# Sheet1.net
KiCad netlist of a schematic drawn in Altium Designer
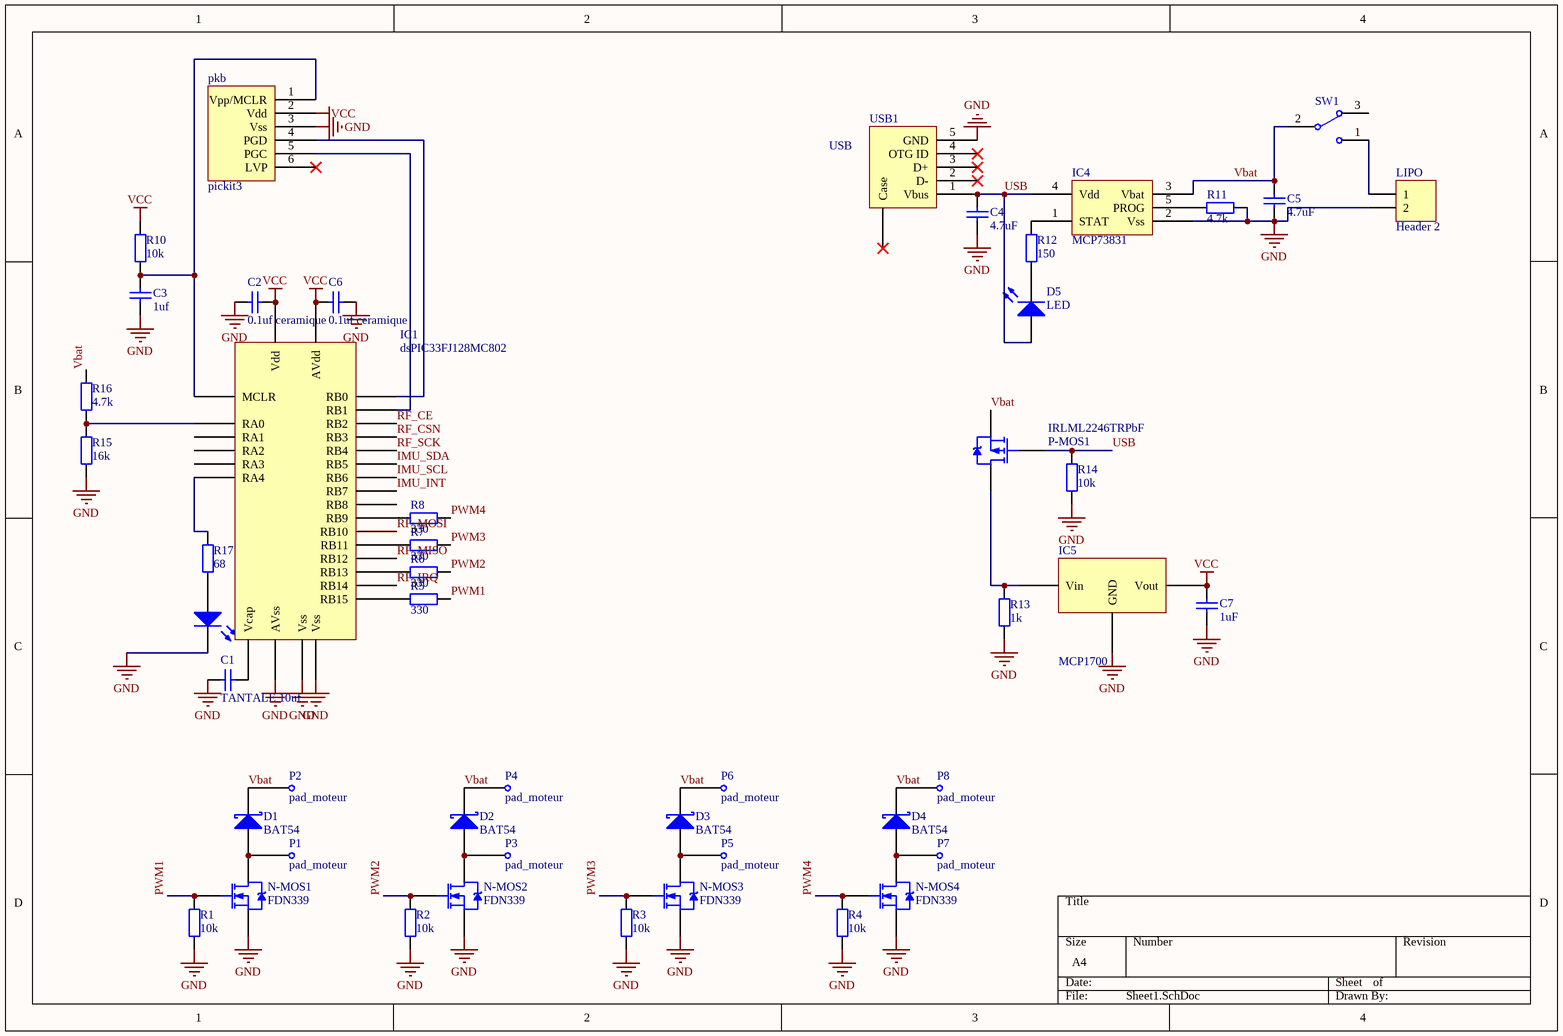
[diagram p0: Sheet1.SchDoc]

(export (version "E")
  (design (tool "Eeschema 10.0.6"))
  (components
    (comp (ref "C1")
      (value "TANTALE 10uf")
      (footprint "cms805")
      (libsource (lib "Integrated_Library1") (part "Capa"))
    )
    (comp (ref "C2")
      (value "0.1uf ceramique")
      (footprint "cms805")
      (libsource (lib "Integrated_Library1") (part "Capa"))
    )
    (comp (ref "C3") (value "1uf") (footprint "cms805") (libsource (lib "Integrated_Library1") (part "Capa")))
    (comp (ref "C4")
      (value "4.7uF")
      (footprint "cms805")
      (libsource (lib "Integrated_Library1") (part "Capa"))
    )
    (comp (ref "C5")
      (value "4.7uF")
      (footprint "cms805")
      (libsource (lib "Integrated_Library1") (part "Capa"))
    )
    (comp (ref "C6")
      (value "0.1uf ceramique")
      (footprint "cms805")
      (libsource (lib "Integrated_Library1") (part "Capa"))
    )
    (comp (ref "C7") (value "1uF") (footprint "cms805") (libsource (lib "Integrated_Library1") (part "Capa")))
    (comp (ref "D1")
      (value "BAT54")
      (footprint "SOT23")
      (libsource (lib "Integrated_Library1") (part "Schottky BAT54"))
    )
    (comp (ref "D2")
      (value "BAT54")
      (footprint "SOT23")
      (libsource (lib "Integrated_Library1") (part "Schottky BAT54"))
    )
    (comp (ref "D3")
      (value "BAT54")
      (footprint "SOT23")
      (libsource (lib "Integrated_Library1") (part "Schottky BAT54"))
    )
    (comp (ref "D4")
      (value "BAT54")
      (footprint "SOT23")
      (libsource (lib "Integrated_Library1") (part "Schottky BAT54"))
    )
    (comp (ref "D5") (value "LED") (footprint "cms1206") (libsource (lib "Integrated_Library1") (part "LED")))
    (comp (ref "D6") (value "LED") (footprint "cms1206") (libsource (lib "Integrated_Library1") (part "LED")))
    (comp (ref "IC1")
      (value "dsPIC33FJ128MC802")
      (footprint "28QFN-S")
      (libsource (lib "Integrated_Library1") (part "dsPIC33FJ128MC802"))
    )
    (comp (ref "IC4")
      (value "MCP73831")
      (footprint "SOT23-5")
      (libsource (lib "Integrated_Library1") (part "MCP73831 Li-Po"))
    )
    (comp (ref "IC5")
      (value "MCP1700")
      (footprint "SOT89")
      (libsource (lib "Integrated_Library1") (part "MCP1700"))
    )
    (comp (ref "IRLML2246TRPbF")
      (value "P-MOS1")
      (footprint "SOT23")
      (libsource (lib "Integrated_Library1") (part "P-MOS"))
    )
    (comp (ref "LIPO")
      (value "Header 2")
      (footprint "HDR1X2")
      (description "Header, 2-Pin")
      (fields (field (name "PUBLISHER") "Altium Limited"))
      (libsource (lib "Miscellaneous Connectors") (part "Header 2"))
    )
    (comp (ref "N-MOS1")
      (value "FDN339")
      (footprint "SuperSOT")
      (libsource (lib "Integrated_Library1") (part "N-MOS FDN339"))
    )
    (comp (ref "N-MOS2")
      (value "FDN339")
      (footprint "SuperSOT")
      (libsource (lib "Integrated_Library1") (part "N-MOS FDN339"))
    )
    (comp (ref "N-MOS3")
      (value "FDN339")
      (footprint "SuperSOT")
      (libsource (lib "Integrated_Library1") (part "N-MOS FDN339"))
    )
    (comp (ref "N-MOS4")
      (value "FDN339")
      (footprint "SuperSOT")
      (libsource (lib "Integrated_Library1") (part "N-MOS FDN339"))
    )
    (comp (ref "P1")
      (value "pad_moteur")
      (footprint "PAD")
      (libsource (lib "Integrated_Library1") (part "pad_moteur"))
    )
    (comp (ref "P2")
      (value "pad_moteur")
      (footprint "PAD")
      (libsource (lib "Integrated_Library1") (part "pad_moteur"))
    )
    (comp (ref "P3")
      (value "pad_moteur")
      (footprint "PAD")
      (libsource (lib "Integrated_Library1") (part "pad_moteur"))
    )
    (comp (ref "P4")
      (value "pad_moteur")
      (footprint "PAD")
      (libsource (lib "Integrated_Library1") (part "pad_moteur"))
    )
    (comp (ref "P5")
      (value "pad_moteur")
      (footprint "PAD")
      (libsource (lib "Integrated_Library1") (part "pad_moteur"))
    )
    (comp (ref "P6")
      (value "pad_moteur")
      (footprint "PAD")
      (libsource (lib "Integrated_Library1") (part "pad_moteur"))
    )
    (comp (ref "P7")
      (value "pad_moteur")
      (footprint "PAD")
      (libsource (lib "Integrated_Library1") (part "pad_moteur"))
    )
    (comp (ref "P8")
      (value "pad_moteur")
      (footprint "PAD")
      (libsource (lib "Integrated_Library1") (part "pad_moteur"))
    )
    (comp (ref "pkb")
      (value "pickit3")
      (footprint "pickit3")
      (libsource (lib "Integrated_Library1") (part "pickit3"))
    )
    (comp (ref "R1")
      (value "10k")
      (footprint "cms805")
      (libsource (lib "Integrated_Library1") (part "Resistance"))
    )
    (comp (ref "R2")
      (value "10k")
      (footprint "cms805")
      (libsource (lib "Integrated_Library1") (part "Resistance"))
    )
    (comp (ref "R3")
      (value "10k")
      (footprint "cms805")
      (libsource (lib "Integrated_Library1") (part "Resistance"))
    )
    (comp (ref "R4")
      (value "10k")
      (footprint "cms805")
      (libsource (lib "Integrated_Library1") (part "Resistance"))
    )
    (comp (ref "R5") (value "330") (footprint "cms805") (libsource (lib "") (part "Resistance_1")))
    (comp (ref "R6") (value "330") (footprint "cms805") (libsource (lib "") (part "Resistance_1")))
    (comp (ref "R7") (value "330") (footprint "cms805") (libsource (lib "") (part "Resistance_1")))
    (comp (ref "R8") (value "330") (footprint "cms805") (libsource (lib "") (part "Resistance_1")))
    (comp (ref "R10")
      (value "10k")
      (footprint "cms805")
      (libsource (lib "Integrated_Library1") (part "Resistance"))
    )
    (comp (ref "R11") (value "4.7k") (footprint "cms805") (libsource (lib "") (part "Resistance_2")))
    (comp (ref "R12") (value "150") (footprint "cms805") (libsource (lib "") (part "Resistance_3")))
    (comp (ref "R13")
      (value "1k")
      (footprint "cms805")
      (libsource (lib "Integrated_Library1") (part "Resistance"))
    )
    (comp (ref "R14")
      (value "10k")
      (footprint "cms805")
      (libsource (lib "Integrated_Library1") (part "Resistance"))
    )
    (comp (ref "R15")
      (value "16k")
      (footprint "cms805")
      (libsource (lib "Integrated_Library1") (part "Resistance"))
    )
    (comp (ref "R16")
      (value "4.7k")
      (footprint "cms805")
      (libsource (lib "Integrated_Library1") (part "Resistance"))
    )
    (comp (ref "R17")
      (value "68")
      (footprint "cms805")
      (libsource (lib "Integrated_Library1") (part "Resistance"))
    )
    (comp (ref "SW1")
      (value "~")
      (footprint "inverseur")
      (libsource (lib "Integrated_Library1") (part "switch"))
    )
    (comp (ref "USB1")
      (value "USB")
      (footprint "USB_con")
      (libsource (lib "Integrated_Library1") (part "USB"))
    )
  )
  (nets
    (net (code "1") (name "/IMU_INT") (class "Default")
      (node (ref "IC1") (pin "16") (pinfunction "RB7_16") (pintype "passive"))
    )
    (net (code "2") (name "/IMU_SCL") (class "Default")
      (node (ref "IC1") (pin "15") (pinfunction "RB6_15") (pintype "passive"))
    )
    (net (code "3") (name "/IMU_SDA") (class "Default")
      (node (ref "IC1") (pin "14") (pinfunction "RB5_14") (pintype "passive"))
    )
    (net (code "4") (name "/PWM1") (class "Default")
      (node (ref "N-MOS1") (pin "1") (pinfunction "G_1") (pintype "passive"))
      (node (ref "R1") (pin "2") (pinfunction "2_2") (pintype "passive"))
      (node (ref "R5") (pin "2") (pinfunction "2_2") (pintype "passive"))
    )
    (net (code "5") (name "/PWM2") (class "Default")
      (node (ref "N-MOS2") (pin "1") (pinfunction "G_1") (pintype "passive"))
      (node (ref "R2") (pin "2") (pinfunction "2_2") (pintype "passive"))
      (node (ref "R6") (pin "2") (pinfunction "2_2") (pintype "passive"))
    )
    (net (code "6") (name "/PWM3") (class "Default")
      (node (ref "N-MOS3") (pin "1") (pinfunction "G_1") (pintype "passive"))
      (node (ref "R3") (pin "2") (pinfunction "2_2") (pintype "passive"))
      (node (ref "R7") (pin "2") (pinfunction "2_2") (pintype "passive"))
    )
    (net (code "7") (name "/PWM4") (class "Default")
      (node (ref "N-MOS4") (pin "1") (pinfunction "G_1") (pintype "passive"))
      (node (ref "R4") (pin "2") (pinfunction "2_2") (pintype "passive"))
      (node (ref "R8") (pin "2") (pinfunction "2_2") (pintype "passive"))
    )
    (net (code "8") (name "/RF_CE") (class "Default")
      (node (ref "IC1") (pin "6") (pinfunction "RB2_6") (pintype "passive"))
    )
    (net (code "9") (name "/RF_CSN") (class "Default")
      (node (ref "IC1") (pin "7") (pinfunction "RB3_7") (pintype "passive"))
    )
    (net (code "10") (name "/RF_IRQ") (class "Default")
      (node (ref "IC1") (pin "25") (pinfunction "RB14_25") (pintype "passive"))
    )
    (net (code "11") (name "/RF_MISO") (class "Default")
      (node (ref "IC1") (pin "23") (pinfunction "RB12_23") (pintype "passive"))
    )
    (net (code "12") (name "/RF_MOSI") (class "Default")
      (node (ref "IC1") (pin "21") (pinfunction "RB10_21") (pintype "passive"))
    )
    (net (code "13") (name "/RF_SCK") (class "Default")
      (node (ref "IC1") (pin "11") (pinfunction "RB4_11") (pintype "passive"))
    )
    (net (code "14") (name "/USB") (class "Default")
      (node (ref "C4") (pin "2") (pinfunction "2_2") (pintype "passive"))
      (node (ref "D5") (pin "1") (pinfunction "A_1") (pintype "passive"))
      (node (ref "IC4") (pin "4") (pinfunction "Vdd_4") (pintype "passive"))
      (node (ref "IRLML2246TRPbF") (pin "1") (pinfunction "G_1") (pintype "passive"))
      (node (ref "R14") (pin "2") (pinfunction "2_2") (pintype "passive"))
      (node (ref "USB1") (pin "1") (pinfunction "Vbus_1") (pintype "passive"))
    )
    (net (code "15") (name "/Vbat") (class "Default")
      (node (ref "C5") (pin "2") (pinfunction "2_2") (pintype "passive"))
      (node (ref "D1") (pin "2") (pinfunction "K_2") (pintype "passive"))
      (node (ref "D2") (pin "2") (pinfunction "K_2") (pintype "passive"))
      (node (ref "D3") (pin "2") (pinfunction "K_2") (pintype "passive"))
      (node (ref "D4") (pin "2") (pinfunction "K_2") (pintype "passive"))
      (node (ref "IC4") (pin "3") (pinfunction "Vbat_3") (pintype "passive"))
      (node (ref "IRLML2246TRPbF") (pin "3") (pinfunction "S_3") (pintype "passive"))
      (node (ref "P2") (pin "1") (pintype "passive"))
      (node (ref "P4") (pin "1") (pintype "passive"))
      (node (ref "P6") (pin "1") (pintype "passive"))
      (node (ref "P8") (pin "1") (pintype "passive"))
      (node (ref "R16") (pin "2") (pinfunction "2_2") (pintype "passive"))
      (node (ref "SW1") (pin "2") (pinfunction "2_2") (pintype "passive"))
    )
    (net (code "16") (name "GND") (class "Default")
      (node (ref "C1") (pin "1") (pinfunction "1_1") (pintype "passive"))
      (node (ref "C2") (pin "1") (pinfunction "1_1") (pintype "passive"))
      (node (ref "C3") (pin "1") (pinfunction "1_1") (pintype "passive"))
      (node (ref "C4") (pin "1") (pinfunction "1_1") (pintype "passive"))
      (node (ref "C5") (pin "1") (pinfunction "1_1") (pintype "passive"))
      (node (ref "C6") (pin "2") (pinfunction "2_2") (pintype "passive"))
      (node (ref "C7") (pin "1") (pinfunction "1_1") (pintype "passive"))
      (node (ref "D6") (pin "2") (pinfunction "K_2") (pintype "passive"))
      (node (ref "IC1") (pin "19") (pinfunction "Vss_19") (pintype "passive"))
      (node (ref "IC1") (pin "27") (pinfunction "AVss_27") (pintype "passive"))
      (node (ref "IC1") (pin "8") (pinfunction "Vss_8") (pintype "passive"))
      (node (ref "IC4") (pin "2") (pinfunction "Vss_2") (pintype "passive"))
      (node (ref "IC5") (pin "1") (pinfunction "GND_1") (pintype "passive"))
      (node (ref "LIPO") (pin "2") (pinfunction "2_2") (pintype "passive"))
      (node (ref "N-MOS1") (pin "3") (pinfunction "S_3") (pintype "passive"))
      (node (ref "N-MOS2") (pin "3") (pinfunction "S_3") (pintype "passive"))
      (node (ref "N-MOS3") (pin "3") (pinfunction "S_3") (pintype "passive"))
      (node (ref "N-MOS4") (pin "3") (pinfunction "S_3") (pintype "passive"))
      (node (ref "R1") (pin "1") (pinfunction "1_1") (pintype "passive"))
      (node (ref "R11") (pin "1") (pinfunction "1_1") (pintype "passive"))
      (node (ref "R13") (pin "1") (pinfunction "1_1") (pintype "passive"))
      (node (ref "R14") (pin "1") (pinfunction "1_1") (pintype "passive"))
      (node (ref "R15") (pin "1") (pinfunction "1_1") (pintype "passive"))
      (node (ref "R2") (pin "1") (pinfunction "1_1") (pintype "passive"))
      (node (ref "R3") (pin "1") (pinfunction "1_1") (pintype "passive"))
      (node (ref "R4") (pin "1") (pinfunction "1_1") (pintype "passive"))
      (node (ref "USB1") (pin "5") (pinfunction "GND_5") (pintype "passive"))
      (node (ref "pkb") (pin "3") (pinfunction "Vss_3") (pintype "passive"))
    )
    (net (code "17") (name "Net-(D1-A)") (class "Default")
      (node (ref "D1") (pin "1") (pinfunction "A_1") (pintype "passive"))
      (node (ref "N-MOS1") (pin "2") (pinfunction "D_2") (pintype "passive"))
      (node (ref "P1") (pin "1") (pintype "passive"))
    )
    (net (code "18") (name "Net-(D2-A)") (class "Default")
      (node (ref "D2") (pin "1") (pinfunction "A_1") (pintype "passive"))
      (node (ref "N-MOS2") (pin "2") (pinfunction "D_2") (pintype "passive"))
      (node (ref "P3") (pin "1") (pintype "passive"))
    )
    (net (code "19") (name "Net-(D3-A)") (class "Default")
      (node (ref "D3") (pin "1") (pinfunction "A_1") (pintype "passive"))
      (node (ref "N-MOS3") (pin "2") (pinfunction "D_2") (pintype "passive"))
      (node (ref "P5") (pin "1") (pintype "passive"))
    )
    (net (code "20") (name "Net-(D4-A)") (class "Default")
      (node (ref "D4") (pin "1") (pinfunction "A_1") (pintype "passive"))
      (node (ref "N-MOS4") (pin "2") (pinfunction "D_2") (pintype "passive"))
      (node (ref "P7") (pin "1") (pintype "passive"))
    )
    (net (code "21") (name "Net-(D5-K)") (class "Default")
      (node (ref "D5") (pin "2") (pinfunction "K_2") (pintype "passive"))
      (node (ref "R12") (pin "2") (pinfunction "2_2") (pintype "passive"))
    )
    (net (code "22") (name "Net-(D6-A)") (class "Default")
      (node (ref "D6") (pin "1") (pinfunction "A_1") (pintype "passive"))
      (node (ref "R17") (pin "1") (pinfunction "1_1") (pintype "passive"))
    )
    (net (code "23") (name "Net-(IC1-MCLR)") (class "Default")
      (node (ref "C3") (pin "2") (pinfunction "2_2") (pintype "passive"))
      (node (ref "IC1") (pin "1") (pinfunction "MCLR_1") (pintype "passive"))
      (node (ref "R10") (pin "1") (pinfunction "1_1") (pintype "passive"))
      (node (ref "pkb") (pin "1") (pinfunction "Vpp/MCLR_1") (pintype "passive"))
    )
    (net (code "24") (name "Net-(IC1-RA0)") (class "Default")
      (node (ref "IC1") (pin "2") (pinfunction "RA0_2") (pintype "passive"))
      (node (ref "R15") (pin "2") (pinfunction "2_2") (pintype "passive"))
      (node (ref "R16") (pin "1") (pinfunction "1_1") (pintype "passive"))
    )
    (net (code "25") (name "Net-(IC1-RA4)") (class "Default")
      (node (ref "IC1") (pin "12") (pinfunction "RA4_12") (pintype "passive"))
      (node (ref "R17") (pin "2") (pinfunction "2_2") (pintype "passive"))
    )
    (net (code "26") (name "Net-(IC1-RB0)") (class "Default")
      (node (ref "IC1") (pin "4") (pinfunction "RB0_4") (pintype "passive"))
      (node (ref "pkb") (pin "4") (pinfunction "PGD_4") (pintype "passive"))
    )
    (net (code "27") (name "Net-(IC1-RB1)") (class "Default")
      (node (ref "IC1") (pin "5") (pinfunction "RB1_5") (pintype "passive"))
      (node (ref "pkb") (pin "5") (pinfunction "PGC_5") (pintype "passive"))
    )
    (net (code "28") (name "Net-(IC1-RB9)") (class "Default")
      (node (ref "IC1") (pin "18") (pinfunction "RB9_18") (pintype "passive"))
      (node (ref "R8") (pin "1") (pinfunction "1_1") (pintype "passive"))
    )
    (net (code "29") (name "Net-(IC1-RB11)") (class "Default")
      (node (ref "IC1") (pin "22") (pinfunction "RB11_22") (pintype "passive"))
      (node (ref "R7") (pin "1") (pinfunction "1_1") (pintype "passive"))
    )
    (net (code "30") (name "Net-(IC1-RB13)") (class "Default")
      (node (ref "IC1") (pin "24") (pinfunction "RB13_24") (pintype "passive"))
      (node (ref "R6") (pin "1") (pinfunction "1_1") (pintype "passive"))
    )
    (net (code "31") (name "Net-(IC1-RB15)") (class "Default")
      (node (ref "IC1") (pin "26") (pinfunction "RB15_26") (pintype "passive"))
      (node (ref "R5") (pin "1") (pinfunction "1_1") (pintype "passive"))
    )
    (net (code "32") (name "Net-(IC1-Vcap)") (class "Default")
      (node (ref "C1") (pin "2") (pinfunction "2_2") (pintype "passive"))
      (node (ref "IC1") (pin "20") (pinfunction "Vcap_20") (pintype "passive"))
    )
    (net (code "33") (name "Net-(IC4-PROG)") (class "Default")
      (node (ref "IC4") (pin "5") (pinfunction "PROG_5") (pintype "passive"))
      (node (ref "R11") (pin "2") (pinfunction "2_2") (pintype "passive"))
    )
    (net (code "34") (name "Net-(IC4-STAT)") (class "Default")
      (node (ref "IC4") (pin "1") (pinfunction "STAT_1") (pintype "passive"))
      (node (ref "R12") (pin "1") (pinfunction "1_1") (pintype "passive"))
    )
    (net (code "35") (name "Net-(IC5-Vin)") (class "Default")
      (node (ref "IC5") (pin "2") (pinfunction "Vin_2") (pintype "passive"))
      (node (ref "IRLML2246TRPbF") (pin "2") (pinfunction "D_2") (pintype "passive"))
      (node (ref "R13") (pin "2") (pinfunction "2_2") (pintype "passive"))
    )
    (net (code "36") (name "Net-(LIPO-Pad1)") (class "Default")
      (node (ref "LIPO") (pin "1") (pinfunction "1_1") (pintype "passive"))
      (node (ref "SW1") (pin "1") (pinfunction "1_1") (pintype "passive"))
    )
    (net (code "37") (name "VCC") (class "Default")
      (node (ref "C2") (pin "2") (pinfunction "2_2") (pintype "passive"))
      (node (ref "C6") (pin "1") (pinfunction "1_1") (pintype "passive"))
      (node (ref "C7") (pin "2") (pinfunction "2_2") (pintype "passive"))
      (node (ref "IC1") (pin "13") (pinfunction "Vdd_13") (pintype "passive"))
      (node (ref "IC1") (pin "28") (pinfunction "AVdd_28") (pintype "passive"))
      (node (ref "IC5") (pin "3") (pinfunction "Vout_3") (pintype "passive"))
      (node (ref "R10") (pin "2") (pinfunction "2_2") (pintype "passive"))
      (node (ref "pkb") (pin "2") (pinfunction "Vdd_2") (pintype "passive"))
    )
    (net (code "38") (name "unconnected-(IC1-RA1-Pad3)") (class "Default")
      (node (ref "IC1") (pin "3") (pinfunction "RA1_3") (pintype "passive"))
    )
    (net (code "39") (name "unconnected-(IC1-RA2-Pad9)") (class "Default")
      (node (ref "IC1") (pin "9") (pinfunction "RA2_9") (pintype "passive"))
    )
    (net (code "40") (name "unconnected-(IC1-RA3-Pad10)") (class "Default")
      (node (ref "IC1") (pin "10") (pinfunction "RA3_10") (pintype "passive"))
    )
    (net (code "41") (name "unconnected-(IC1-RB8-Pad17)") (class "Default")
      (node (ref "IC1") (pin "17") (pinfunction "RB8_17") (pintype "passive"))
    )
    (net (code "42") (name "unconnected-(SW1-Pad3)") (class "Default")
      (node (ref "SW1") (pin "3") (pinfunction "3_3") (pintype "passive"))
    )
    (net (code "43") (name "unconnected-(USB1-Case-Pad0)") (class "Default")
      (node (ref "USB1") (pin "0") (pinfunction "Case_0") (pintype "passive+no_connect"))
    )
    (net (code "44") (name "unconnected-(USB1-D+-Pad3)") (class "Default")
      (node (ref "USB1") (pin "3") (pinfunction "D+_3") (pintype "passive+no_connect"))
    )
    (net (code "45") (name "unconnected-(USB1-D--Pad2)") (class "Default")
      (node (ref "USB1") (pin "2") (pinfunction "D-_2") (pintype "passive+no_connect"))
    )
    (net (code "46") (name "unconnected-(USB1-OTG_ID-Pad4)") (class "Default")
      (node (ref "USB1") (pin "4") (pinfunction "OTG_ID_4") (pintype "passive+no_connect"))
    )
    (net (code "47") (name "unconnected-(pkb-LVP-Pad6)") (class "Default")
      (node (ref "pkb") (pin "6") (pinfunction "LVP_6") (pintype "passive+no_connect"))
    )
  )
)
